# XLIN1_7-2048SQ_TE0_MB.net
KiCad netlist of a schematic drawn in Altium Designer
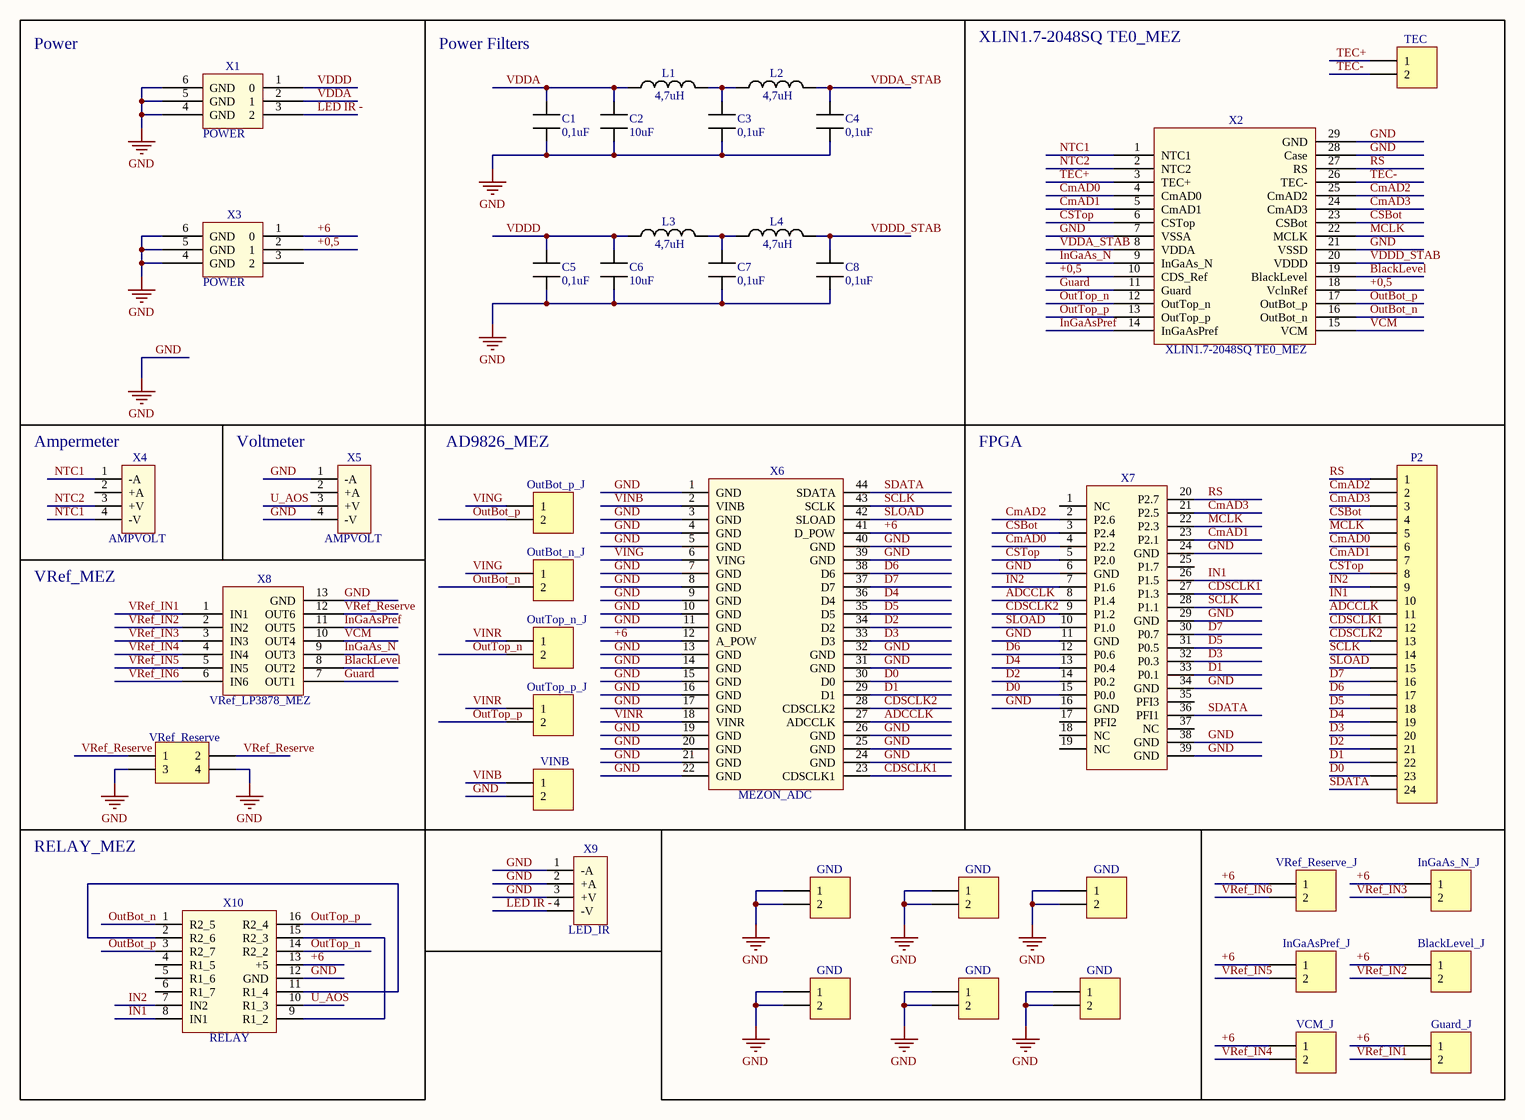
[diagram p0: XLIN1.7-2048SQ TE0_MB.SchDoc]

(export (version "E")
  (design (tool "Eeschema 10.0.6"))
  (components
    (comp (ref "C1")
      (value "0,1uF")
      (footprint "aab_Passive:CAP_0603")
      (libsource (lib "aab_Schlib") (part "CAP"))
    )
    (comp (ref "C2")
      (value "10uF")
      (footprint "aab_Passive:CAP_1812")
      (libsource (lib "aab_Schlib") (part "CAP"))
    )
    (comp (ref "C3")
      (value "0,1uF")
      (footprint "aab_Passive:CAP_0603")
      (libsource (lib "aab_Schlib") (part "CAP"))
    )
    (comp (ref "C4")
      (value "0,1uF")
      (footprint "aab_Passive:CAP_0603")
      (libsource (lib "aab_Schlib") (part "CAP"))
    )
    (comp (ref "C5")
      (value "0,1uF")
      (footprint "aab_Passive:CAP_0603")
      (libsource (lib "aab_Schlib") (part "CAP"))
    )
    (comp (ref "C6")
      (value "10uF")
      (footprint "aab_Passive:CAP_1812")
      (libsource (lib "aab_Schlib") (part "CAP"))
    )
    (comp (ref "C7")
      (value "0,1uF")
      (footprint "aab_Passive:CAP_0603")
      (libsource (lib "aab_Schlib") (part "CAP"))
    )
    (comp (ref "C8")
      (value "0,1uF")
      (footprint "aab_Passive:CAP_0603")
      (libsource (lib "aab_Schlib") (part "CAP"))
    )
    (comp (ref "L1")
      (value "4,7uH")
      (footprint "aab_Passive:IND_0805")
      (libsource (lib "aab_Schlib") (part "IND"))
    )
    (comp (ref "L2")
      (value "4,7uH")
      (footprint "aab_Passive:IND_0805")
      (libsource (lib "aab_Schlib") (part "IND"))
    )
    (comp (ref "L3")
      (value "4,7uH")
      (footprint "aab_Passive:IND_0805")
      (libsource (lib "aab_Schlib") (part "IND"))
    )
    (comp (ref "L4")
      (value "4,7uH")
      (footprint "aab_Passive:IND_0805")
      (libsource (lib "aab_Schlib") (part "IND"))
    )
    (comp (ref "P1")
      (value "TEC")
      (footprint "HDR1X2")
      (description "Header, 2-Pin")
      (fields (field (name "PUBLISHER") "Altium Limited"))
      (libsource (lib "Miscellaneous Connectors") (part "Header 2"))
    )
    (comp (ref "P2")
      (value "Header 24")
      (footprint "HDR1X24")
      (description "Header, 24-Pin")
      (fields (field (name "PUBLISHER") "Altium Limited"))
      (libsource (lib "Miscellaneous Connectors") (part "Header 24"))
    )
    (comp (ref "P3")
      (value "OutBot_p_J")
      (footprint "HDR1X2")
      (description "Header, 2-Pin")
      (fields (field (name "PUBLISHER") "Altium Limited"))
      (libsource (lib "Miscellaneous Connectors") (part "Header 2"))
    )
    (comp (ref "P4")
      (value "OutBot_n_J")
      (footprint "HDR1X2")
      (description "Header, 2-Pin")
      (fields (field (name "PUBLISHER") "Altium Limited"))
      (libsource (lib "Miscellaneous Connectors") (part "Header 2"))
    )
    (comp (ref "P5")
      (value "OutTop_n_J")
      (footprint "HDR1X2")
      (description "Header, 2-Pin")
      (fields (field (name "PUBLISHER") "Altium Limited"))
      (libsource (lib "Miscellaneous Connectors") (part "Header 2"))
    )
    (comp (ref "P6")
      (value "OutTop_p_J")
      (footprint "HDR1X2")
      (description "Header, 2-Pin")
      (fields (field (name "PUBLISHER") "Altium Limited"))
      (libsource (lib "Miscellaneous Connectors") (part "Header 2"))
    )
    (comp (ref "P7")
      (value "VRef_Reserve")
      (footprint "HDR2X2")
      (description "Header, 2-Pin, Dual row")
      (fields (field (name "PUBLISHER") "Altium Limited"))
      (libsource (lib "Miscellaneous Connectors") (part "Header 2X2"))
    )
    (comp (ref "P8")
      (value "VINB")
      (footprint "HDR1X2")
      (description "Header, 2-Pin")
      (fields (field (name "PUBLISHER") "Altium Limited"))
      (libsource (lib "Miscellaneous Connectors") (part "Header 2"))
    )
    (comp (ref "P9")
      (value "VRef_Reserve_J")
      (footprint "HDR1X2")
      (description "Header, 2-Pin")
      (fields (field (name "PUBLISHER") "Altium Limited"))
      (libsource (lib "Miscellaneous Connectors") (part "Header 2"))
    )
    (comp (ref "P10")
      (value "InGaAs_N_J")
      (footprint "HDR1X2")
      (description "Header, 2-Pin")
      (fields (field (name "PUBLISHER") "Altium Limited"))
      (libsource (lib "Miscellaneous Connectors") (part "Header 2"))
    )
    (comp (ref "P11")
      (value "GND")
      (footprint "HDR1X2")
      (description "Header, 2-Pin")
      (fields (field (name "PUBLISHER") "Altium Limited"))
      (libsource (lib "Miscellaneous Connectors") (part "Header 2"))
    )
    (comp (ref "P12")
      (value "GND")
      (footprint "HDR1X2")
      (description "Header, 2-Pin")
      (fields (field (name "PUBLISHER") "Altium Limited"))
      (libsource (lib "Miscellaneous Connectors") (part "Header 2"))
    )
    (comp (ref "P13")
      (value "GND")
      (footprint "HDR1X2")
      (description "Header, 2-Pin")
      (fields (field (name "PUBLISHER") "Altium Limited"))
      (libsource (lib "Miscellaneous Connectors") (part "Header 2"))
    )
    (comp (ref "P14")
      (value "InGaAsPref_J")
      (footprint "HDR1X2")
      (description "Header, 2-Pin")
      (fields (field (name "PUBLISHER") "Altium Limited"))
      (libsource (lib "Miscellaneous Connectors") (part "Header 2"))
    )
    (comp (ref "P15")
      (value "BlackLevel_J")
      (footprint "HDR1X2")
      (description "Header, 2-Pin")
      (fields (field (name "PUBLISHER") "Altium Limited"))
      (libsource (lib "Miscellaneous Connectors") (part "Header 2"))
    )
    (comp (ref "P16")
      (value "GND")
      (footprint "HDR1X2")
      (description "Header, 2-Pin")
      (fields (field (name "PUBLISHER") "Altium Limited"))
      (libsource (lib "Miscellaneous Connectors") (part "Header 2"))
    )
    (comp (ref "P17")
      (value "GND")
      (footprint "HDR1X2")
      (description "Header, 2-Pin")
      (fields (field (name "PUBLISHER") "Altium Limited"))
      (libsource (lib "Miscellaneous Connectors") (part "Header 2"))
    )
    (comp (ref "P18")
      (value "GND")
      (footprint "HDR1X2")
      (description "Header, 2-Pin")
      (fields (field (name "PUBLISHER") "Altium Limited"))
      (libsource (lib "Miscellaneous Connectors") (part "Header 2"))
    )
    (comp (ref "P19")
      (value "VCM_J")
      (footprint "HDR1X2")
      (description "Header, 2-Pin")
      (fields (field (name "PUBLISHER") "Altium Limited"))
      (libsource (lib "Miscellaneous Connectors") (part "Header 2"))
    )
    (comp (ref "P20")
      (value "Guard_J")
      (footprint "HDR1X2")
      (description "Header, 2-Pin")
      (fields (field (name "PUBLISHER") "Altium Limited"))
      (libsource (lib "Miscellaneous Connectors") (part "Header 2"))
    )
    (comp (ref "X1") (value "POWER") (footprint "POWER") (libsource (lib "vpl_Schlib") (part "POWER")))
    (comp (ref "X2")
      (value "XLIN1.7-2048SQ TE0_MEZ")
      (footprint "aab_Active:XLIN1.7-2048SQ TE0_MEZ")
      (libsource (lib "aab_Schlib") (part "XLIN1.7-2048SQ TE0_MEZ"))
    )
    (comp (ref "X3") (value "POWER") (footprint "POWER") (libsource (lib "vpl_Schlib") (part "POWER")))
    (comp (ref "X4")
      (value "AMPVOLT")
      (footprint "AMP_VOLTMETER")
      (libsource (lib "vpl_Schlib") (part "AMP_VOLTMETER"))
    )
    (comp (ref "X5")
      (value "AMPVOLT")
      (footprint "AMP_VOLTMETER")
      (libsource (lib "vpl_Schlib") (part "AMP_VOLTMETER"))
    )
    (comp (ref "X6")
      (value "MEZON_ADC")
      (footprint "MEZON_ADC")
      (libsource (lib "vpl_Schlib") (part "MEZON_ADC"))
    )
    (comp (ref "X7")
      (value "CHEAP_CON_37_FEMALE")
      (footprint "CHEAP_CONN_FEMALE")
      (libsource (lib "vpl_Schlib") (part "CHEAP_CON_37_FEMALE"))
    )
    (comp (ref "X8")
      (value "VRef_LP3878_MEZ")
      (footprint "aab_Active:VRef_LP3878_MEZ")
      (libsource (lib "aab_Schlib") (part "VRef_LP3878_MEZ"))
    )
    (comp (ref "X9")
      (value "LED_IR")
      (footprint "AMP_VOLTMETER")
      (libsource (lib "vpl_Schlib") (part "AMP_VOLTMETER"))
    )
    (comp (ref "X10")
      (value "RELAY")
      (footprint "RELAY_MODULE")
      (libsource (lib "vpl_Schlib") (part "MEZON_RELAY"))
    )
  )
  (nets
    (net (code "1") (name "/+0,5") (class "Default")
      (node (ref "X2") (pin "10") (pinfunction "CDS_Ref_10") (pintype "passive"))
      (node (ref "X2") (pin "18") (pinfunction "VclnRef_18") (pintype "passive"))
      (node (ref "X3") (pin "2") (pinfunction "1_2") (pintype "passive"))
    )
    (net (code "2") (name "/+6") (class "Default")
      (node (ref "P10") (pin "1") (pinfunction "1_1") (pintype "passive"))
      (node (ref "P14") (pin "1") (pinfunction "1_1") (pintype "passive"))
      (node (ref "P15") (pin "1") (pinfunction "1_1") (pintype "passive"))
      (node (ref "P19") (pin "1") (pinfunction "1_1") (pintype "passive"))
      (node (ref "P20") (pin "1") (pinfunction "1_1") (pintype "passive"))
      (node (ref "P9") (pin "1") (pinfunction "1_1") (pintype "passive"))
      (node (ref "X10") (pin "13") (pinfunction "+5_13") (pintype "passive"))
      (node (ref "X3") (pin "1") (pinfunction "0_1") (pintype "passive"))
      (node (ref "X6") (pin "12") (pinfunction "A_POW_12") (pintype "passive"))
      (node (ref "X6") (pin "41") (pinfunction "D_POW_41") (pintype "passive"))
    )
    (net (code "3") (name "/ADCCLK") (class "Default")
      (node (ref "P2") (pin "11") (pinfunction "11_11") (pintype "passive"))
      (node (ref "X6") (pin "27") (pinfunction "ADCCLK_27") (pintype "passive"))
      (node (ref "X7") (pin "8") (pinfunction "P1.4_8") (pintype "passive"))
    )
    (net (code "4") (name "/BlackLevel") (class "Default")
      (node (ref "X2") (pin "19") (pinfunction "BlackLevel_19") (pintype "passive"))
      (node (ref "X8") (pin "8") (pinfunction "OUT2_8") (pintype "passive"))
    )
    (net (code "5") (name "/CDSCLK1") (class "Default")
      (node (ref "P2") (pin "12") (pinfunction "12_12") (pintype "passive"))
      (node (ref "X6") (pin "23") (pinfunction "CDSCLK1_23") (pintype "passive"))
      (node (ref "X7") (pin "27") (pinfunction "P1.3_27") (pintype "passive"))
    )
    (net (code "6") (name "/CDSCLK2") (class "Default")
      (node (ref "P2") (pin "13") (pinfunction "13_13") (pintype "passive"))
      (node (ref "X6") (pin "28") (pinfunction "CDSCLK2_28") (pintype "passive"))
      (node (ref "X7") (pin "9") (pinfunction "P1.2_9") (pintype "passive"))
    )
    (net (code "7") (name "/CSBot") (class "Default")
      (node (ref "P2") (pin "4") (pinfunction "4_4") (pintype "passive"))
      (node (ref "X2") (pin "23") (pinfunction "CSBot_23") (pintype "passive"))
      (node (ref "X7") (pin "3") (pinfunction "P2.4_3") (pintype "passive"))
    )
    (net (code "8") (name "/CSTop") (class "Default")
      (node (ref "P2") (pin "8") (pinfunction "8_8") (pintype "passive"))
      (node (ref "X2") (pin "6") (pinfunction "CSTop_6") (pintype "passive"))
      (node (ref "X7") (pin "5") (pinfunction "P2.0_5") (pintype "passive"))
    )
    (net (code "9") (name "/CmAD0") (class "Default")
      (node (ref "P2") (pin "6") (pinfunction "6_6") (pintype "passive"))
      (node (ref "X2") (pin "4") (pinfunction "CmAD0_4") (pintype "passive"))
      (node (ref "X7") (pin "4") (pinfunction "P2.2_4") (pintype "passive"))
    )
    (net (code "10") (name "/CmAD1") (class "Default")
      (node (ref "P2") (pin "7") (pinfunction "7_7") (pintype "passive"))
      (node (ref "X2") (pin "5") (pinfunction "CmAD1_5") (pintype "passive"))
      (node (ref "X7") (pin "23") (pinfunction "P2.1_23") (pintype "passive"))
    )
    (net (code "11") (name "/CmAD2") (class "Default")
      (node (ref "P2") (pin "2") (pinfunction "2_2") (pintype "passive"))
      (node (ref "X2") (pin "25") (pinfunction "CmAD2_25") (pintype "passive"))
      (node (ref "X7") (pin "2") (pinfunction "P2.6_2") (pintype "passive"))
    )
    (net (code "12") (name "/CmAD3") (class "Default")
      (node (ref "P2") (pin "3") (pinfunction "3_3") (pintype "passive"))
      (node (ref "X2") (pin "24") (pinfunction "CmAD3_24") (pintype "passive"))
      (node (ref "X7") (pin "21") (pinfunction "P2.5_21") (pintype "passive"))
    )
    (net (code "13") (name "/D0") (class "Default")
      (node (ref "P2") (pin "23") (pinfunction "23_23") (pintype "passive"))
      (node (ref "X6") (pin "30") (pinfunction "D0_30") (pintype "passive"))
      (node (ref "X7") (pin "15") (pinfunction "P0.0_15") (pintype "passive"))
    )
    (net (code "14") (name "/D1") (class "Default")
      (node (ref "P2") (pin "22") (pinfunction "22_22") (pintype "passive"))
      (node (ref "X6") (pin "29") (pinfunction "D1_29") (pintype "passive"))
      (node (ref "X7") (pin "33") (pinfunction "P0.1_33") (pintype "passive"))
    )
    (net (code "15") (name "/D2") (class "Default")
      (node (ref "P2") (pin "21") (pinfunction "21_21") (pintype "passive"))
      (node (ref "X6") (pin "34") (pinfunction "D2_34") (pintype "passive"))
      (node (ref "X7") (pin "14") (pinfunction "P0.2_14") (pintype "passive"))
    )
    (net (code "16") (name "/D3") (class "Default")
      (node (ref "P2") (pin "20") (pinfunction "20_20") (pintype "passive"))
      (node (ref "X6") (pin "33") (pinfunction "D3_33") (pintype "passive"))
      (node (ref "X7") (pin "32") (pinfunction "P0.3_32") (pintype "passive"))
    )
    (net (code "17") (name "/D4") (class "Default")
      (node (ref "P2") (pin "19") (pinfunction "19_19") (pintype "passive"))
      (node (ref "X6") (pin "36") (pinfunction "D4_36") (pintype "passive"))
      (node (ref "X7") (pin "13") (pinfunction "P0.4_13") (pintype "passive"))
    )
    (net (code "18") (name "/D5") (class "Default")
      (node (ref "P2") (pin "18") (pinfunction "18_18") (pintype "passive"))
      (node (ref "X6") (pin "35") (pinfunction "D5_35") (pintype "passive"))
      (node (ref "X7") (pin "31") (pinfunction "P0.5_31") (pintype "passive"))
    )
    (net (code "19") (name "/D6") (class "Default")
      (node (ref "P2") (pin "17") (pinfunction "17_17") (pintype "passive"))
      (node (ref "X6") (pin "38") (pinfunction "D6_38") (pintype "passive"))
      (node (ref "X7") (pin "12") (pinfunction "P0.6_12") (pintype "passive"))
    )
    (net (code "20") (name "/D7") (class "Default")
      (node (ref "P2") (pin "16") (pinfunction "16_16") (pintype "passive"))
      (node (ref "X6") (pin "37") (pinfunction "D7_37") (pintype "passive"))
      (node (ref "X7") (pin "30") (pinfunction "P0.7_30") (pintype "passive"))
    )
    (net (code "21") (name "/Guard") (class "Default")
      (node (ref "X2") (pin "11") (pinfunction "Guard_11") (pintype "passive"))
      (node (ref "X8") (pin "7") (pinfunction "OUT1_7") (pintype "passive"))
    )
    (net (code "22") (name "/IN1") (class "Default")
      (node (ref "P2") (pin "10") (pinfunction "10_10") (pintype "passive"))
      (node (ref "X10") (pin "8") (pinfunction "IN1_8") (pintype "passive"))
      (node (ref "X7") (pin "26") (pinfunction "P1.5_26") (pintype "passive"))
    )
    (net (code "23") (name "/IN2") (class "Default")
      (node (ref "P2") (pin "9") (pinfunction "9_9") (pintype "passive"))
      (node (ref "X10") (pin "7") (pinfunction "IN2_7") (pintype "passive"))
      (node (ref "X7") (pin "7") (pinfunction "P1.6_7") (pintype "passive"))
    )
    (net (code "24") (name "/InGaAsPref") (class "Default")
      (node (ref "X2") (pin "14") (pinfunction "InGaAsPref_14") (pintype "passive"))
      (node (ref "X8") (pin "11") (pinfunction "OUT5_11") (pintype "passive"))
    )
    (net (code "25") (name "/InGaAs_N") (class "Default")
      (node (ref "X2") (pin "9") (pinfunction "InGaAs_N_9") (pintype "passive"))
      (node (ref "X8") (pin "9") (pinfunction "OUT3_9") (pintype "passive"))
    )
    (net (code "26") (name "/LED IR -") (class "Default")
      (node (ref "X1") (pin "3") (pinfunction "2_3") (pintype "passive"))
      (node (ref "X9") (pin "4") (pinfunction "-V_4") (pintype "passive"))
    )
    (net (code "27") (name "/MCLK") (class "Default")
      (node (ref "P2") (pin "5") (pinfunction "5_5") (pintype "passive"))
      (node (ref "X2") (pin "22") (pinfunction "MCLK_22") (pintype "passive"))
      (node (ref "X7") (pin "22") (pinfunction "P2.3_22") (pintype "passive"))
    )
    (net (code "28") (name "/NTC1") (class "Default")
      (node (ref "X2") (pin "1") (pinfunction "NTC1_1") (pintype "passive"))
      (node (ref "X4") (pin "1") (pinfunction "-A_1") (pintype "passive"))
      (node (ref "X4") (pin "4") (pinfunction "-V_4") (pintype "passive"))
    )
    (net (code "29") (name "/NTC2") (class "Default")
      (node (ref "X2") (pin "2") (pinfunction "NTC2_2") (pintype "passive"))
      (node (ref "X4") (pin "3") (pinfunction "+V_3") (pintype "passive"))
    )
    (net (code "30") (name "/OutBot_n") (class "Default")
      (node (ref "P4") (pin "2") (pinfunction "2_2") (pintype "passive"))
      (node (ref "X10") (pin "1") (pinfunction "R2_5_1") (pintype "passive"))
      (node (ref "X2") (pin "16") (pinfunction "OutBot_n_16") (pintype "passive"))
    )
    (net (code "31") (name "/OutBot_p") (class "Default")
      (node (ref "P3") (pin "2") (pinfunction "2_2") (pintype "passive"))
      (node (ref "X10") (pin "3") (pinfunction "R2_7_3") (pintype "passive"))
      (node (ref "X2") (pin "17") (pinfunction "OutBot_p_17") (pintype "passive"))
    )
    (net (code "32") (name "/OutTop_n") (class "Default")
      (node (ref "P5") (pin "2") (pinfunction "2_2") (pintype "passive"))
      (node (ref "X10") (pin "14") (pinfunction "R2_2_14") (pintype "passive"))
      (node (ref "X2") (pin "12") (pinfunction "OutTop_n_12") (pintype "passive"))
    )
    (net (code "33") (name "/OutTop_p") (class "Default")
      (node (ref "P6") (pin "2") (pinfunction "2_2") (pintype "passive"))
      (node (ref "X10") (pin "16") (pinfunction "R2_4_16") (pintype "passive"))
      (node (ref "X2") (pin "13") (pinfunction "OutTop_p_13") (pintype "passive"))
    )
    (net (code "34") (name "/RS") (class "Default")
      (node (ref "P2") (pin "1") (pinfunction "1_1") (pintype "passive"))
      (node (ref "X2") (pin "27") (pinfunction "RS_27") (pintype "passive"))
      (node (ref "X7") (pin "20") (pinfunction "P2.7_20") (pintype "passive"))
    )
    (net (code "35") (name "/SCLK") (class "Default")
      (node (ref "P2") (pin "14") (pinfunction "14_14") (pintype "passive"))
      (node (ref "X6") (pin "43") (pinfunction "SCLK_43") (pintype "passive"))
      (node (ref "X7") (pin "28") (pinfunction "P1.1_28") (pintype "passive"))
    )
    (net (code "36") (name "/SDATA") (class "Default")
      (node (ref "P2") (pin "24") (pinfunction "24_24") (pintype "passive"))
      (node (ref "X6") (pin "44") (pinfunction "SDATA_44") (pintype "passive"))
      (node (ref "X7") (pin "36") (pinfunction "PFI1_36") (pintype "passive"))
    )
    (net (code "37") (name "/SLOAD") (class "Default")
      (node (ref "P2") (pin "15") (pinfunction "15_15") (pintype "passive"))
      (node (ref "X6") (pin "42") (pinfunction "SLOAD_42") (pintype "passive"))
      (node (ref "X7") (pin "10") (pinfunction "P1.0_10") (pintype "passive"))
    )
    (net (code "38") (name "/TEC+") (class "Default")
      (node (ref "P1") (pin "1") (pinfunction "1_1") (pintype "passive"))
      (node (ref "X2") (pin "3") (pinfunction "TEC+_3") (pintype "passive"))
    )
    (net (code "39") (name "/TEC-") (class "Default")
      (node (ref "P1") (pin "2") (pinfunction "2_2") (pintype "passive"))
      (node (ref "X2") (pin "26") (pinfunction "TEC-_26") (pintype "passive"))
    )
    (net (code "40") (name "/U_AOS") (class "Default")
      (node (ref "X10") (pin "10") (pinfunction "R1_3_10") (pintype "passive"))
      (node (ref "X5") (pin "3") (pinfunction "+V_3") (pintype "passive"))
    )
    (net (code "41") (name "/VCM") (class "Default")
      (node (ref "X2") (pin "15") (pinfunction "VCM_15") (pintype "passive"))
      (node (ref "X8") (pin "10") (pinfunction "OUT4_10") (pintype "passive"))
    )
    (net (code "42") (name "/VDDA") (class "Default")
      (node (ref "C1") (pin "2") (pinfunction "2_2") (pintype "passive"))
      (node (ref "C2") (pin "2") (pinfunction "2_2") (pintype "passive"))
      (node (ref "L1") (pin "1") (pinfunction "1_1") (pintype "passive"))
      (node (ref "X1") (pin "2") (pinfunction "1_2") (pintype "passive"))
    )
    (net (code "43") (name "/VDDA_STAB") (class "Default")
      (node (ref "C4") (pin "2") (pinfunction "2_2") (pintype "passive"))
      (node (ref "L2") (pin "2") (pinfunction "2_2") (pintype "passive"))
      (node (ref "X2") (pin "8") (pinfunction "VDDA_8") (pintype "passive"))
    )
    (net (code "44") (name "/VDDD") (class "Default")
      (node (ref "C5") (pin "2") (pinfunction "2_2") (pintype "passive"))
      (node (ref "C6") (pin "2") (pinfunction "2_2") (pintype "passive"))
      (node (ref "L3") (pin "1") (pinfunction "1_1") (pintype "passive"))
      (node (ref "X1") (pin "1") (pinfunction "0_1") (pintype "passive"))
    )
    (net (code "45") (name "/VDDD_STAB") (class "Default")
      (node (ref "C8") (pin "2") (pinfunction "2_2") (pintype "passive"))
      (node (ref "L4") (pin "2") (pinfunction "2_2") (pintype "passive"))
      (node (ref "X2") (pin "20") (pinfunction "VDDD_20") (pintype "passive"))
    )
    (net (code "46") (name "/VINB") (class "Default")
      (node (ref "P8") (pin "1") (pinfunction "1_1") (pintype "passive"))
      (node (ref "X6") (pin "2") (pinfunction "VINB_2") (pintype "passive"))
    )
    (net (code "47") (name "/VING") (class "Default")
      (node (ref "P3") (pin "1") (pinfunction "1_1") (pintype "passive"))
      (node (ref "P4") (pin "1") (pinfunction "1_1") (pintype "passive"))
      (node (ref "X6") (pin "6") (pinfunction "VING_6") (pintype "passive"))
    )
    (net (code "48") (name "/VINR") (class "Default")
      (node (ref "P5") (pin "1") (pinfunction "1_1") (pintype "passive"))
      (node (ref "P6") (pin "1") (pinfunction "1_1") (pintype "passive"))
      (node (ref "X6") (pin "18") (pinfunction "VINR_18") (pintype "passive"))
    )
    (net (code "49") (name "/VRef_IN1") (class "Default")
      (node (ref "P20") (pin "2") (pinfunction "2_2") (pintype "passive"))
      (node (ref "X8") (pin "1") (pinfunction "IN1_1") (pintype "passive"))
    )
    (net (code "50") (name "/VRef_IN2") (class "Default")
      (node (ref "P15") (pin "2") (pinfunction "2_2") (pintype "passive"))
      (node (ref "X8") (pin "2") (pinfunction "IN2_2") (pintype "passive"))
    )
    (net (code "51") (name "/VRef_IN3") (class "Default")
      (node (ref "P10") (pin "2") (pinfunction "2_2") (pintype "passive"))
      (node (ref "X8") (pin "3") (pinfunction "IN3_3") (pintype "passive"))
    )
    (net (code "52") (name "/VRef_IN4") (class "Default")
      (node (ref "P19") (pin "2") (pinfunction "2_2") (pintype "passive"))
      (node (ref "X8") (pin "4") (pinfunction "IN4_4") (pintype "passive"))
    )
    (net (code "53") (name "/VRef_IN5") (class "Default")
      (node (ref "P14") (pin "2") (pinfunction "2_2") (pintype "passive"))
      (node (ref "X8") (pin "5") (pinfunction "IN5_5") (pintype "passive"))
    )
    (net (code "54") (name "/VRef_IN6") (class "Default")
      (node (ref "P9") (pin "2") (pinfunction "2_2") (pintype "passive"))
      (node (ref "X8") (pin "6") (pinfunction "IN6_6") (pintype "passive"))
    )
    (net (code "55") (name "/VRef_Reserve") (class "Default")
      (node (ref "P7") (pin "1") (pinfunction "1_1") (pintype "passive"))
      (node (ref "P7") (pin "2") (pinfunction "2_2") (pintype "passive"))
      (node (ref "X8") (pin "12") (pinfunction "OUT6_12") (pintype "passive"))
    )
    (net (code "56") (name "GND") (class "Default")
      (node (ref "C1") (pin "1") (pinfunction "1_1") (pintype "passive"))
      (node (ref "C2") (pin "1") (pinfunction "1_1") (pintype "passive"))
      (node (ref "C3") (pin "1") (pinfunction "1_1") (pintype "passive"))
      (node (ref "C4") (pin "1") (pinfunction "1_1") (pintype "passive"))
      (node (ref "C5") (pin "1") (pinfunction "1_1") (pintype "passive"))
      (node (ref "C6") (pin "1") (pinfunction "1_1") (pintype "passive"))
      (node (ref "C7") (pin "1") (pinfunction "1_1") (pintype "passive"))
      (node (ref "C8") (pin "1") (pinfunction "1_1") (pintype "passive"))
      (node (ref "P11") (pin "1") (pinfunction "1_1") (pintype "passive"))
      (node (ref "P11") (pin "2") (pinfunction "2_2") (pintype "passive"))
      (node (ref "P12") (pin "1") (pinfunction "1_1") (pintype "passive"))
      (node (ref "P12") (pin "2") (pinfunction "2_2") (pintype "passive"))
      (node (ref "P13") (pin "1") (pinfunction "1_1") (pintype "passive"))
      (node (ref "P13") (pin "2") (pinfunction "2_2") (pintype "passive"))
      (node (ref "P16") (pin "1") (pinfunction "1_1") (pintype "passive"))
      (node (ref "P16") (pin "2") (pinfunction "2_2") (pintype "passive"))
      (node (ref "P17") (pin "1") (pinfunction "1_1") (pintype "passive"))
      (node (ref "P17") (pin "2") (pinfunction "2_2") (pintype "passive"))
      (node (ref "P18") (pin "1") (pinfunction "1_1") (pintype "passive"))
      (node (ref "P18") (pin "2") (pinfunction "2_2") (pintype "passive"))
      (node (ref "P7") (pin "3") (pinfunction "3_3") (pintype "passive"))
      (node (ref "P7") (pin "4") (pinfunction "4_4") (pintype "passive"))
      (node (ref "P8") (pin "2") (pinfunction "2_2") (pintype "passive"))
      (node (ref "X1") (pin "4") (pinfunction "GND_4") (pintype "passive"))
      (node (ref "X1") (pin "5") (pinfunction "GND_5") (pintype "passive"))
      (node (ref "X1") (pin "6") (pinfunction "GND_6") (pintype "passive"))
      (node (ref "X10") (pin "12") (pinfunction "GND_12") (pintype "passive"))
      (node (ref "X2") (pin "21") (pinfunction "VSSD_21") (pintype "passive"))
      (node (ref "X2") (pin "28") (pinfunction "Case_28") (pintype "passive"))
      (node (ref "X2") (pin "29") (pinfunction "GND_29") (pintype "passive"))
      (node (ref "X2") (pin "7") (pinfunction "VSSA_7") (pintype "passive"))
      (node (ref "X3") (pin "4") (pinfunction "GND_4") (pintype "passive"))
      (node (ref "X3") (pin "5") (pinfunction "GND_5") (pintype "passive"))
      (node (ref "X3") (pin "6") (pinfunction "GND_6") (pintype "passive"))
      (node (ref "X5") (pin "1") (pinfunction "-A_1") (pintype "passive"))
      (node (ref "X5") (pin "4") (pinfunction "-V_4") (pintype "passive"))
      (node (ref "X6") (pin "1") (pinfunction "GND_1") (pintype "passive"))
      (node (ref "X6") (pin "10") (pinfunction "GND_10") (pintype "passive"))
      (node (ref "X6") (pin "11") (pinfunction "GND_11") (pintype "passive"))
      (node (ref "X6") (pin "13") (pinfunction "GND_13") (pintype "passive"))
      (node (ref "X6") (pin "14") (pinfunction "GND_14") (pintype "passive"))
      (node (ref "X6") (pin "15") (pinfunction "GND_15") (pintype "passive"))
      (node (ref "X6") (pin "16") (pinfunction "GND_16") (pintype "passive"))
      (node (ref "X6") (pin "17") (pinfunction "GND_17") (pintype "passive"))
      (node (ref "X6") (pin "19") (pinfunction "GND_19") (pintype "passive"))
      (node (ref "X6") (pin "20") (pinfunction "GND_20") (pintype "passive"))
      (node (ref "X6") (pin "21") (pinfunction "GND_21") (pintype "passive"))
      (node (ref "X6") (pin "22") (pinfunction "GND_22") (pintype "passive"))
      (node (ref "X6") (pin "24") (pinfunction "GND_24") (pintype "passive"))
      (node (ref "X6") (pin "25") (pinfunction "GND_25") (pintype "passive"))
      (node (ref "X6") (pin "26") (pinfunction "GND_26") (pintype "passive"))
      (node (ref "X6") (pin "3") (pinfunction "GND_3") (pintype "passive"))
      (node (ref "X6") (pin "31") (pinfunction "GND_31") (pintype "passive"))
      (node (ref "X6") (pin "32") (pinfunction "GND_32") (pintype "passive"))
      (node (ref "X6") (pin "39") (pinfunction "GND_39") (pintype "passive"))
      (node (ref "X6") (pin "4") (pinfunction "GND_4") (pintype "passive"))
      (node (ref "X6") (pin "40") (pinfunction "GND_40") (pintype "passive"))
      (node (ref "X6") (pin "5") (pinfunction "GND_5") (pintype "passive"))
      (node (ref "X6") (pin "7") (pinfunction "GND_7") (pintype "passive"))
      (node (ref "X6") (pin "8") (pinfunction "GND_8") (pintype "passive"))
      (node (ref "X6") (pin "9") (pinfunction "GND_9") (pintype "passive"))
      (node (ref "X7") (pin "11") (pinfunction "GND_11") (pintype "passive"))
      (node (ref "X7") (pin "16") (pinfunction "GND_16") (pintype "passive"))
      (node (ref "X7") (pin "24") (pinfunction "GND_24") (pintype "passive"))
      (node (ref "X7") (pin "29") (pinfunction "GND_29") (pintype "passive"))
      (node (ref "X7") (pin "34") (pinfunction "GND_34") (pintype "passive"))
      (node (ref "X7") (pin "38") (pinfunction "GND_38") (pintype "passive"))
      (node (ref "X7") (pin "39") (pinfunction "GND_39") (pintype "passive"))
      (node (ref "X7") (pin "6") (pinfunction "GND_6") (pintype "passive"))
      (node (ref "X8") (pin "13") (pinfunction "GND_13") (pintype "passive"))
      (node (ref "X9") (pin "1") (pinfunction "-A_1") (pintype "passive"))
      (node (ref "X9") (pin "2") (pinfunction "+A_2") (pintype "passive"))
      (node (ref "X9") (pin "3") (pinfunction "+V_3") (pintype "passive"))
    )
    (net (code "57") (name "Net-(C3-Pad2)") (class "Default")
      (node (ref "C3") (pin "2") (pinfunction "2_2") (pintype "passive"))
      (node (ref "L1") (pin "2") (pinfunction "2_2") (pintype "passive"))
      (node (ref "L2") (pin "1") (pinfunction "1_1") (pintype "passive"))
    )
    (net (code "58") (name "Net-(C7-Pad2)") (class "Default")
      (node (ref "C7") (pin "2") (pinfunction "2_2") (pintype "passive"))
      (node (ref "L3") (pin "2") (pinfunction "2_2") (pintype "passive"))
      (node (ref "L4") (pin "1") (pinfunction "1_1") (pintype "passive"))
    )
    (net (code "59") (name "Net-(X10-R1_2)") (class "Default")
      (node (ref "X10") (pin "15") (pinfunction "R2_3_15") (pintype "passive"))
      (node (ref "X10") (pin "9") (pinfunction "R1_2_9") (pintype "passive"))
    )
    (net (code "60") (name "Net-(X10-R1_4)") (class "Default")
      (node (ref "X10") (pin "11") (pinfunction "R1_4_11") (pintype "passive"))
      (node (ref "X10") (pin "2") (pinfunction "R2_6_2") (pintype "passive"))
    )
    (net (code "61") (name "unconnected-(X3-2-Pad3)") (class "Default")
      (node (ref "X3") (pin "3") (pinfunction "2_3") (pintype "passive"))
    )
    (net (code "62") (name "unconnected-(X4-+A-Pad2)") (class "Default")
      (node (ref "X4") (pin "2") (pinfunction "+A_2") (pintype "passive"))
    )
    (net (code "63") (name "unconnected-(X5-+A-Pad2)") (class "Default")
      (node (ref "X5") (pin "2") (pinfunction "+A_2") (pintype "passive"))
    )
    (net (code "64") (name "unconnected-(X7-NC-Pad1)") (class "Default")
      (node (ref "X7") (pin "1") (pinfunction "NC_1") (pintype "passive"))
    )
    (net (code "65") (name "unconnected-(X7-NC-Pad18)") (class "Default")
      (node (ref "X7") (pin "18") (pinfunction "NC_18") (pintype "passive"))
    )
    (net (code "66") (name "unconnected-(X7-NC-Pad19)") (class "Default")
      (node (ref "X7") (pin "19") (pinfunction "NC_19") (pintype "passive"))
    )
    (net (code "67") (name "unconnected-(X7-NC-Pad37)") (class "Default")
      (node (ref "X7") (pin "37") (pinfunction "NC_37") (pintype "passive"))
    )
    (net (code "68") (name "unconnected-(X7-P1.7-Pad25)") (class "Default")
      (node (ref "X7") (pin "25") (pinfunction "P1.7_25") (pintype "passive"))
    )
    (net (code "69") (name "unconnected-(X7-PFI2-Pad17)") (class "Default")
      (node (ref "X7") (pin "17") (pinfunction "PFI2_17") (pintype "passive"))
    )
    (net (code "70") (name "unconnected-(X7-PFI3-Pad35)") (class "Default")
      (node (ref "X7") (pin "35") (pinfunction "PFI3_35") (pintype "passive"))
    )
    (net (code "71") (name "unconnected-(X10-R1_5-Pad4)") (class "Default")
      (node (ref "X10") (pin "4") (pinfunction "R1_5_4") (pintype "passive"))
    )
    (net (code "72") (name "unconnected-(X10-R1_6-Pad5)") (class "Default")
      (node (ref "X10") (pin "5") (pinfunction "R1_6_5") (pintype "passive"))
    )
    (net (code "73") (name "unconnected-(X10-R1_7-Pad6)") (class "Default")
      (node (ref "X10") (pin "6") (pinfunction "R1_7_6") (pintype "passive"))
    )
  )
)
